# Key_Reset.net
KiCad netlist of a schematic drawn in Altium Designer
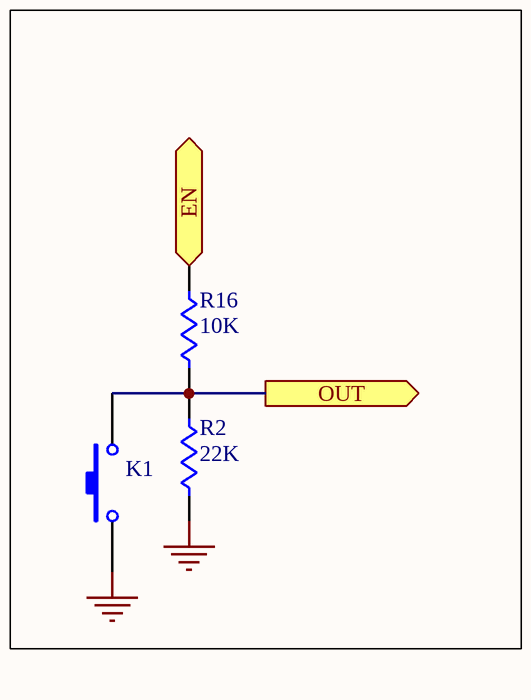
[diagram p0: Key_Reset.SchDoc]

(export (version "E")
  (design (tool "Eeschema 10.0.6"))
  (components
    (comp (ref "K1")
      (value "SW-PB")
      (footprint "SPST-2_2")
      (description "Switch")
      (fields (field (name "MANUFACTURER") "Generic Components") (field (name "PUBLISHER") "Altium Limited"))
      (libsource (lib "Miscellaneous Devices") (part "SW-PB"))
    )
    (comp (ref "R2")
      (value "22K")
      (footprint "0805")
      (description "Resistor")
      (fields (field (name "MANUFACTURER") "Generic Components") (field (name "PUBLISHER") "Altium Limited"))
      (libsource (lib "Miscellaneous Devices") (part "Res1"))
    )
    (comp (ref "R16")
      (value "10K")
      (footprint "0805")
      (description "Resistor")
      (fields (field (name "MANUFACTURER") "Generic Components") (field (name "PUBLISHER") "Altium Limited"))
      (libsource (lib "Miscellaneous Devices") (part "Res1"))
    )
  )
  (nets
    (net (code "1") (name "/EN") (class "Default")
      (node (ref "R16") (pin "2") (pinfunction "2_2") (pintype "passive"))
    )
    (net (code "2") (name "/OUT") (class "Default")
      (node (ref "K1") (pin "2") (pinfunction "2_2") (pintype "passive"))
      (node (ref "R16") (pin "1") (pinfunction "1_1") (pintype "passive"))
      (node (ref "R2") (pin "2") (pinfunction "2_2") (pintype "passive"))
    )
    (net (code "3") (name "GND") (class "Default")
      (node (ref "K1") (pin "1") (pinfunction "1_1") (pintype "passive"))
      (node (ref "R2") (pin "1") (pinfunction "1_1") (pintype "passive"))
    )
  )
)
